# luci2_device.net
KiCad netlist of a schematic drawn in EAGLE
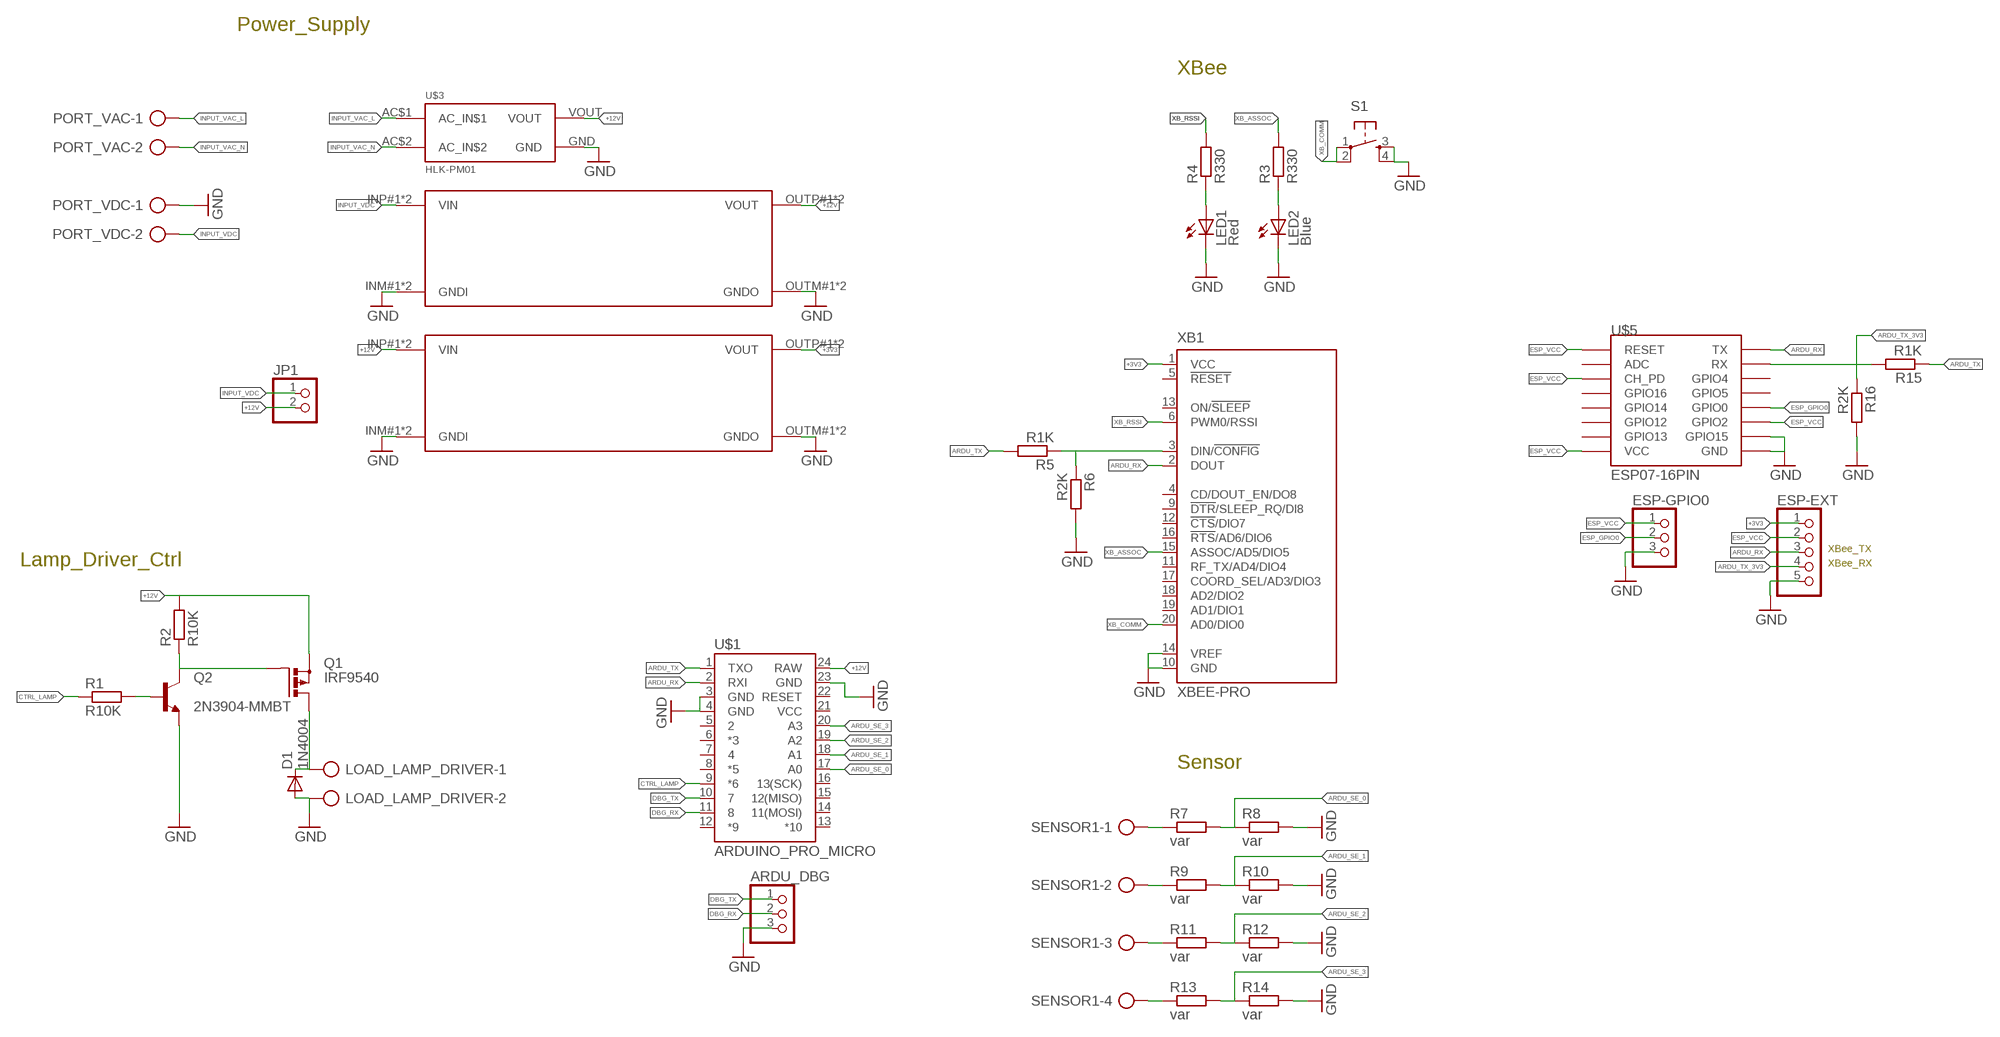
[diagram p0: schematic, sheet 1]

(export (version "E")
  (design (tool "Eeschema 10.0.6"))
  (components
    (comp (ref "ARDU_DBG")
      (value "HEADER-1X3ROUND")
      (footprint "eagle-import:1X03_ROUND")
      (libsource (lib "eagle-import") (part "HEADER-1X3ROUND"))
    )
    (comp (ref "D1")
      (value "1N4004")
      (footprint "eagle-import:DO41-10")
      (libsource (lib "eagle-import") (part "1N4004"))
    )
    (comp (ref "ESP-EXT")
      (value "HEADER-1X5ROUND")
      (footprint "eagle-import:1X05_ROUND")
      (libsource (lib "eagle-import") (part "HEADER-1X5ROUND"))
    )
    (comp (ref "ESP-GPIO0")
      (value "HEADER-1X3ROUND")
      (footprint "eagle-import:1X03_ROUND")
      (libsource (lib "eagle-import") (part "HEADER-1X3ROUND"))
    )
    (comp (ref "JP1")
      (value "HEADER-1X2ROUND")
      (footprint "eagle-import:1X02_ROUND")
      (libsource (lib "eagle-import") (part "HEADER-1X2ROUND"))
    )
    (comp (ref "LED1")
      (value "Red")
      (footprint "eagle-import:CHIPLED_0805")
      (libsource (lib "eagle-import") (part "LEDCHIPLED_0805"))
    )
    (comp (ref "LED2")
      (value "Blue")
      (footprint "eagle-import:CHIPLED_0805")
      (libsource (lib "eagle-import") (part "LEDCHIPLED_0805"))
    )
    (comp (ref "LOAD_LAMP_DRIVER")
      (value "AK300/2")
      (footprint "eagle-import:AK300_2")
      (libsource (lib "eagle-import") (part "AK300/2"))
    )
    (comp (ref "PORT_VAC")
      (value "AK300/2")
      (footprint "eagle-import:AK300_2")
      (libsource (lib "eagle-import") (part "AK300/2"))
    )
    (comp (ref "PORT_VDC")
      (value "AK300/2")
      (footprint "eagle-import:AK300_2")
      (libsource (lib "eagle-import") (part "AK300/2"))
    )
    (comp (ref "Q1")
      (value "IRF9540")
      (footprint "eagle-import:TO220BV")
      (libsource (lib "eagle-import") (part "PMOSFET_PTO220BV"))
    )
    (comp (ref "Q2")
      (value "2N3904-MMBT")
      (footprint "eagle-import:SOT23")
      (libsource (lib "eagle-import") (part "2N3904-MMBT"))
    )
    (comp (ref "R1")
      (value "R10K")
      (footprint "eagle-import:M0805")
      (libsource (lib "eagle-import") (part "R-EU_M0805"))
    )
    (comp (ref "R2")
      (value "R10K")
      (footprint "eagle-import:M0805")
      (libsource (lib "eagle-import") (part "R-EU_M0805"))
    )
    (comp (ref "R3")
      (value "R330")
      (footprint "eagle-import:M0805")
      (libsource (lib "eagle-import") (part "R-EU_M0805"))
    )
    (comp (ref "R4")
      (value "R330")
      (footprint "eagle-import:M0805")
      (libsource (lib "eagle-import") (part "R-EU_M0805"))
    )
    (comp (ref "R5")
      (value "R1K")
      (footprint "eagle-import:M0805")
      (libsource (lib "eagle-import") (part "R-EU_M0805"))
    )
    (comp (ref "R6")
      (value "R2K")
      (footprint "eagle-import:M0805")
      (libsource (lib "eagle-import") (part "R-EU_M0805"))
    )
    (comp (ref "R7")
      (value "var")
      (footprint "eagle-import:M0805")
      (libsource (lib "eagle-import") (part "R-EU_M0805"))
    )
    (comp (ref "R8")
      (value "var")
      (footprint "eagle-import:M0805")
      (libsource (lib "eagle-import") (part "R-EU_M0805"))
    )
    (comp (ref "R9")
      (value "var")
      (footprint "eagle-import:M0805")
      (libsource (lib "eagle-import") (part "R-EU_M0805"))
    )
    (comp (ref "R10")
      (value "var")
      (footprint "eagle-import:M0805")
      (libsource (lib "eagle-import") (part "R-EU_M0805"))
    )
    (comp (ref "R11")
      (value "var")
      (footprint "eagle-import:M0805")
      (libsource (lib "eagle-import") (part "R-EU_M0805"))
    )
    (comp (ref "R12")
      (value "var")
      (footprint "eagle-import:M0805")
      (libsource (lib "eagle-import") (part "R-EU_M0805"))
    )
    (comp (ref "R13")
      (value "var")
      (footprint "eagle-import:M0805")
      (libsource (lib "eagle-import") (part "R-EU_M0805"))
    )
    (comp (ref "R14")
      (value "var")
      (footprint "eagle-import:M0805")
      (libsource (lib "eagle-import") (part "R-EU_M0805"))
    )
    (comp (ref "R15")
      (value "R1K")
      (footprint "eagle-import:M0805")
      (libsource (lib "eagle-import") (part "R-EU_M0805"))
    )
    (comp (ref "R16")
      (value "R2K")
      (footprint "eagle-import:M0805")
      (libsource (lib "eagle-import") (part "R-EU_M0805"))
    )
    (comp (ref "S1")
      (value "TAC_SWITCHPTH")
      (footprint "eagle-import:TACTILE-PTH")
      (libsource (lib "eagle-import") (part "TAC_SWITCHPTH"))
    )
    (comp (ref "SENSOR1")
      (value "AK300/4")
      (footprint "eagle-import:AK300_4")
      (libsource (lib "eagle-import") (part "AK300/4"))
    )
    (comp (ref "U$1")
      (value "ARDUINO_PRO_MICRO")
      (footprint "eagle-import:ARDUINO_PRO_MICRO")
      (libsource (lib "eagle-import") (part "ARDUINO_PRO_MICRO"))
    )
    (comp (ref "U$2")
      (value "DCDCMODULE_SMALL")
      (footprint "eagle-import:DCDCMODULE-SMALL")
      (libsource (lib "eagle-import") (part "DCDCMODULE_SMALL"))
    )
    (comp (ref "U$3")
      (value "HLK-PM01")
      (footprint "eagle-import:HLK-PM01")
      (libsource (lib "eagle-import") (part "HLK-PM01"))
    )
    (comp (ref "U$4")
      (value "DCDCMODULE_SMALL")
      (footprint "eagle-import:DCDCMODULE-SMALL")
      (libsource (lib "eagle-import") (part "DCDCMODULE_SMALL"))
    )
    (comp (ref "U$5")
      (value "ESP07-16PIN")
      (footprint "eagle-import:ESP07-16PIN")
      (libsource (lib "eagle-import") (part "ESP07-16PIN"))
    )
    (comp (ref "XB1")
      (value "XBEE-PRO")
      (footprint "eagle-import:XBEE-PRO")
      (libsource (lib "eagle-import") (part "XBEE-PRO"))
    )
  )
  (nets
    (net (code "1") (name "+3V3") (class "Default")
      (node (ref "ESP-EXT") (pin "1") (pinfunction "1_1") (pintype "passive"))
      (node (ref "U$2") (pin "OUTP#1") (pinfunction "VOUT_OUTP#1") (pintype "bidirectional"))
      (node (ref "U$2") (pin "OUTP#2") (pinfunction "VOUT_OUTP#2") (pintype "bidirectional"))
      (node (ref "XB1") (pin "1") (pinfunction "VCC_1") (pintype "power_in"))
    )
    (net (code "2") (name "+12V") (class "Default")
      (node (ref "JP1") (pin "2") (pinfunction "2_2") (pintype "passive"))
      (node (ref "Q1") (pin "S") (pinfunction "S_S") (pintype "passive"))
      (node (ref "R2") (pin "2") (pinfunction "2_2") (pintype "passive"))
      (node (ref "U$1") (pin "24") (pinfunction "RAW_24") (pintype "bidirectional"))
      (node (ref "U$2") (pin "INP#1") (pinfunction "VIN_INP#1") (pintype "bidirectional"))
      (node (ref "U$2") (pin "INP#2") (pinfunction "VIN_INP#2") (pintype "bidirectional"))
      (node (ref "U$3") (pin "VOUT") (pinfunction "VOUT_VOUT") (pintype "bidirectional"))
      (node (ref "U$4") (pin "OUTP#1") (pinfunction "VOUT_OUTP#1") (pintype "bidirectional"))
      (node (ref "U$4") (pin "OUTP#2") (pinfunction "VOUT_OUTP#2") (pintype "bidirectional"))
    )
    (net (code "3") (name "ARDU_RX") (class "Default")
      (node (ref "ESP-EXT") (pin "3") (pinfunction "3_3") (pintype "passive"))
      (node (ref "U$1") (pin "2") (pinfunction "RXI_2") (pintype "bidirectional"))
      (node (ref "U$5") (pin "TX") (pinfunction "TX_TX") (pintype "bidirectional"))
      (node (ref "XB1") (pin "2") (pinfunction "DOUT_2") (pintype "output"))
    )
    (net (code "4") (name "ARDU_SE_0") (class "Default")
      (node (ref "R7") (pin "2") (pinfunction "2_2") (pintype "passive"))
      (node (ref "R8") (pin "1") (pinfunction "1_1") (pintype "passive"))
      (node (ref "U$1") (pin "17") (pinfunction "A0_17") (pintype "bidirectional"))
    )
    (net (code "5") (name "ARDU_SE_1") (class "Default")
      (node (ref "R10") (pin "1") (pinfunction "1_1") (pintype "passive"))
      (node (ref "R9") (pin "2") (pinfunction "2_2") (pintype "passive"))
      (node (ref "U$1") (pin "18") (pinfunction "A1_18") (pintype "bidirectional"))
    )
    (net (code "6") (name "ARDU_SE_2") (class "Default")
      (node (ref "R11") (pin "2") (pinfunction "2_2") (pintype "passive"))
      (node (ref "R12") (pin "1") (pinfunction "1_1") (pintype "passive"))
      (node (ref "U$1") (pin "19") (pinfunction "A2_19") (pintype "bidirectional"))
    )
    (net (code "7") (name "ARDU_SE_3") (class "Default")
      (node (ref "R13") (pin "2") (pinfunction "2_2") (pintype "passive"))
      (node (ref "R14") (pin "1") (pinfunction "1_1") (pintype "passive"))
      (node (ref "U$1") (pin "20") (pinfunction "A3_20") (pintype "bidirectional"))
    )
    (net (code "8") (name "ARDU_TX") (class "Default")
      (node (ref "R15") (pin "1") (pinfunction "1_1") (pintype "passive"))
      (node (ref "R5") (pin "2") (pinfunction "2_2") (pintype "passive"))
      (node (ref "U$1") (pin "1") (pinfunction "TXO_1") (pintype "bidirectional"))
    )
    (net (code "9") (name "ARDU_TX_3V3") (class "Default")
      (node (ref "ESP-EXT") (pin "4") (pinfunction "4_4") (pintype "passive"))
      (node (ref "R15") (pin "2") (pinfunction "2_2") (pintype "passive"))
      (node (ref "R16") (pin "1") (pinfunction "1_1") (pintype "passive"))
      (node (ref "U$5") (pin "RX") (pinfunction "RX_RX") (pintype "bidirectional"))
    )
    (net (code "10") (name "CTRL_LAMP") (class "Default")
      (node (ref "R1") (pin "1") (pinfunction "1_1") (pintype "passive"))
      (node (ref "U$1") (pin "9") (pinfunction "*6_9") (pintype "bidirectional"))
    )
    (net (code "11") (name "DBG_RX") (class "Default")
      (node (ref "ARDU_DBG") (pin "2") (pinfunction "2_2") (pintype "passive"))
      (node (ref "U$1") (pin "11") (pinfunction "8_11") (pintype "bidirectional"))
    )
    (net (code "12") (name "DBG_TX") (class "Default")
      (node (ref "ARDU_DBG") (pin "1") (pinfunction "1_1") (pintype "passive"))
      (node (ref "U$1") (pin "10") (pinfunction "7_10") (pintype "bidirectional"))
    )
    (net (code "13") (name "ESP_GPIO0") (class "Default")
      (node (ref "ESP-GPIO0") (pin "2") (pinfunction "2_2") (pintype "passive"))
      (node (ref "U$5") (pin "GPIO0") (pinfunction "GPIO0_GPIO0") (pintype "bidirectional"))
    )
    (net (code "14") (name "ESP_VCC") (class "Default")
      (node (ref "ESP-EXT") (pin "2") (pinfunction "2_2") (pintype "passive"))
      (node (ref "ESP-GPIO0") (pin "1") (pinfunction "1_1") (pintype "passive"))
      (node (ref "U$5") (pin "CH_PD") (pinfunction "CH_PD_CH_PD") (pintype "bidirectional"))
      (node (ref "U$5") (pin "GPIO2") (pinfunction "GPIO2_GPIO2") (pintype "bidirectional"))
      (node (ref "U$5") (pin "REST") (pinfunction "RESET_REST") (pintype "bidirectional"))
      (node (ref "U$5") (pin "VCC") (pinfunction "VCC_VCC") (pintype "bidirectional"))
    )
    (net (code "15") (name "GND") (class "Default")
      (node (ref "ARDU_DBG") (pin "3") (pinfunction "3_3") (pintype "passive"))
      (node (ref "D1") (pin "A") (pinfunction "A_A") (pintype "passive"))
      (node (ref "ESP-EXT") (pin "5") (pinfunction "5_5") (pintype "passive"))
      (node (ref "ESP-GPIO0") (pin "3") (pinfunction "3_3") (pintype "passive"))
      (node (ref "LED1") (pin "C") (pinfunction "C_C") (pintype "passive"))
      (node (ref "LED2") (pin "C") (pinfunction "C_C") (pintype "passive"))
      (node (ref "LOAD_LAMP_DRIVER") (pin "2") (pinfunction "KL_2") (pintype "passive"))
      (node (ref "PORT_VDC") (pin "1") (pinfunction "KL_1") (pintype "passive"))
      (node (ref "Q2") (pin "2") (pinfunction "E_2") (pintype "passive"))
      (node (ref "R10") (pin "2") (pinfunction "2_2") (pintype "passive"))
      (node (ref "R12") (pin "2") (pinfunction "2_2") (pintype "passive"))
      (node (ref "R14") (pin "2") (pinfunction "2_2") (pintype "passive"))
      (node (ref "R16") (pin "2") (pinfunction "2_2") (pintype "passive"))
      (node (ref "R6") (pin "2") (pinfunction "2_2") (pintype "passive"))
      (node (ref "R8") (pin "2") (pinfunction "2_2") (pintype "passive"))
      (node (ref "S1") (pin "3") (pinfunction "3_3") (pintype "passive"))
      (node (ref "S1") (pin "4") (pinfunction "4_4") (pintype "passive"))
      (node (ref "U$1") (pin "23") (pinfunction "GND_23") (pintype "bidirectional"))
      (node (ref "U$1") (pin "3") (pinfunction "GND_3") (pintype "bidirectional"))
      (node (ref "U$1") (pin "4") (pinfunction "GND_4") (pintype "bidirectional"))
      (node (ref "U$2") (pin "INM#1") (pinfunction "GNDI_INM#1") (pintype "bidirectional"))
      (node (ref "U$2") (pin "INM#2") (pinfunction "GNDI_INM#2") (pintype "bidirectional"))
      (node (ref "U$2") (pin "OUTM#1") (pinfunction "GNDO_OUTM#1") (pintype "bidirectional"))
      (node (ref "U$2") (pin "OUTM#2") (pinfunction "GNDO_OUTM#2") (pintype "bidirectional"))
      (node (ref "U$3") (pin "GND") (pinfunction "GND_GND") (pintype "bidirectional"))
      (node (ref "U$4") (pin "INM#1") (pinfunction "GNDI_INM#1") (pintype "bidirectional"))
      (node (ref "U$4") (pin "INM#2") (pinfunction "GNDI_INM#2") (pintype "bidirectional"))
      (node (ref "U$4") (pin "OUTM#1") (pinfunction "GNDO_OUTM#1") (pintype "bidirectional"))
      (node (ref "U$4") (pin "OUTM#2") (pinfunction "GNDO_OUTM#2") (pintype "bidirectional"))
      (node (ref "U$5") (pin "GND") (pinfunction "GND_GND") (pintype "bidirectional"))
      (node (ref "U$5") (pin "GPIO15") (pinfunction "GPIO15_GPIO15") (pintype "bidirectional"))
      (node (ref "XB1") (pin "10") (pinfunction "GND_10") (pintype "power_in"))
      (node (ref "XB1") (pin "14") (pinfunction "VREF_14") (pintype "input"))
    )
    (net (code "16") (name "INPUT_VAC_L") (class "Default")
      (node (ref "PORT_VAC") (pin "1") (pinfunction "KL_1") (pintype "passive"))
      (node (ref "U$3") (pin "AC$1") (pinfunction "AC_IN$1_AC$1") (pintype "bidirectional"))
    )
    (net (code "17") (name "INPUT_VAC_N") (class "Default")
      (node (ref "PORT_VAC") (pin "2") (pinfunction "KL_2") (pintype "passive"))
      (node (ref "U$3") (pin "AC$2") (pinfunction "AC_IN$2_AC$2") (pintype "bidirectional"))
    )
    (net (code "18") (name "INPUT_VDC") (class "Default")
      (node (ref "JP1") (pin "1") (pinfunction "1_1") (pintype "passive"))
      (node (ref "PORT_VDC") (pin "2") (pinfunction "KL_2") (pintype "passive"))
      (node (ref "U$4") (pin "INP#1") (pinfunction "VIN_INP#1") (pintype "bidirectional"))
      (node (ref "U$4") (pin "INP#2") (pinfunction "VIN_INP#2") (pintype "bidirectional"))
    )
    (net (code "19") (name "Net-(LED1-PadA)") (class "Default")
      (node (ref "LED1") (pin "A") (pinfunction "A_A") (pintype "passive"))
      (node (ref "R4") (pin "1") (pinfunction "1_1") (pintype "passive"))
    )
    (net (code "20") (name "Net-(LED2-PadA)") (class "Default")
      (node (ref "LED2") (pin "A") (pinfunction "A_A") (pintype "passive"))
      (node (ref "R3") (pin "1") (pinfunction "1_1") (pintype "passive"))
    )
    (net (code "21") (name "Net-(LOAD_LAMP_DRIVERA-KL)") (class "Default")
      (node (ref "D1") (pin "C") (pinfunction "C_C") (pintype "passive"))
      (node (ref "LOAD_LAMP_DRIVER") (pin "1") (pinfunction "KL_1") (pintype "passive"))
      (node (ref "Q1") (pin "D") (pinfunction "D_D") (pintype "passive"))
    )
    (net (code "22") (name "Net-(Q2-B)") (class "Default")
      (node (ref "Q2") (pin "1") (pinfunction "B_1") (pintype "passive"))
      (node (ref "R1") (pin "2") (pinfunction "2_2") (pintype "passive"))
    )
    (net (code "23") (name "Net-(Q2-C)") (class "Default")
      (node (ref "Q1") (pin "G") (pinfunction "G_G") (pintype "passive"))
      (node (ref "Q2") (pin "3") (pinfunction "C_3") (pintype "passive"))
      (node (ref "R2") (pin "1") (pinfunction "1_1") (pintype "passive"))
    )
    (net (code "24") (name "Net-(SENSOR1A-KL)") (class "Default")
      (node (ref "R7") (pin "1") (pinfunction "1_1") (pintype "passive"))
      (node (ref "SENSOR1") (pin "1") (pinfunction "KL_1") (pintype "passive"))
    )
    (net (code "25") (name "Net-(SENSOR1B-KL)") (class "Default")
      (node (ref "R9") (pin "1") (pinfunction "1_1") (pintype "passive"))
      (node (ref "SENSOR1") (pin "2") (pinfunction "KL_2") (pintype "passive"))
    )
    (net (code "26") (name "Net-(SENSOR1C-KL)") (class "Default")
      (node (ref "R11") (pin "1") (pinfunction "1_1") (pintype "passive"))
      (node (ref "SENSOR1") (pin "3") (pinfunction "KL_3") (pintype "passive"))
    )
    (net (code "27") (name "Net-(SENSOR1D-KL)") (class "Default")
      (node (ref "R13") (pin "1") (pinfunction "1_1") (pintype "passive"))
      (node (ref "SENSOR1") (pin "4") (pinfunction "KL_4") (pintype "passive"))
    )
    (net (code "28") (name "Net-(XB1-DIN{slash}~{CONFIG})") (class "Default")
      (node (ref "R5") (pin "1") (pinfunction "1_1") (pintype "passive"))
      (node (ref "R6") (pin "1") (pinfunction "1_1") (pintype "passive"))
      (node (ref "XB1") (pin "3") (pinfunction "DIN/~{CONFIG}_3") (pintype "input"))
    )
    (net (code "29") (name "XB_ASSOC") (class "Default")
      (node (ref "R3") (pin "2") (pinfunction "2_2") (pintype "passive"))
      (node (ref "XB1") (pin "15") (pinfunction "ASSOC/AD5/DIO5_15") (pintype "bidirectional"))
    )
    (net (code "30") (name "XB_COMM") (class "Default")
      (node (ref "S1") (pin "1") (pinfunction "1_1") (pintype "passive"))
      (node (ref "S1") (pin "2") (pinfunction "2_2") (pintype "passive"))
      (node (ref "XB1") (pin "20") (pinfunction "AD0/DIO0_20") (pintype "bidirectional"))
    )
    (net (code "31") (name "XB_RSSI") (class "Default")
      (node (ref "R4") (pin "2") (pinfunction "2_2") (pintype "passive"))
      (node (ref "XB1") (pin "6") (pinfunction "PWM0/RSSI_6") (pintype "output"))
    )
    (net (code "32") (name "unconnected-(U$1-*3-Pad6)") (class "Default")
      (node (ref "U$1") (pin "6") (pinfunction "*3_6") (pintype "bidirectional"))
    )
    (net (code "33") (name "unconnected-(U$1-*5-Pad8)") (class "Default")
      (node (ref "U$1") (pin "8") (pinfunction "*5_8") (pintype "bidirectional"))
    )
    (net (code "34") (name "unconnected-(U$1-*9-Pad12)") (class "Default")
      (node (ref "U$1") (pin "12") (pinfunction "*9_12") (pintype "bidirectional"))
    )
    (net (code "35") (name "unconnected-(U$1-*10-Pad13)") (class "Default")
      (node (ref "U$1") (pin "13") (pinfunction "*10_13") (pintype "bidirectional"))
    )
    (net (code "36") (name "unconnected-(U$1-2-Pad5)") (class "Default")
      (node (ref "U$1") (pin "5") (pinfunction "2_5") (pintype "bidirectional"))
    )
    (net (code "37") (name "unconnected-(U$1-4-Pad7)") (class "Default")
      (node (ref "U$1") (pin "7") (pinfunction "4_7") (pintype "bidirectional"))
    )
    (net (code "38") (name "unconnected-(U$1-11(MOSI)-Pad14)") (class "Default")
      (node (ref "U$1") (pin "14") (pinfunction "11(MOSI)_14") (pintype "bidirectional"))
    )
    (net (code "39") (name "unconnected-(U$1-12(MISO)-Pad15)") (class "Default")
      (node (ref "U$1") (pin "15") (pinfunction "12(MISO)_15") (pintype "bidirectional"))
    )
    (net (code "40") (name "unconnected-(U$1-13(SCK)-Pad16)") (class "Default")
      (node (ref "U$1") (pin "16") (pinfunction "13(SCK)_16") (pintype "bidirectional"))
    )
    (net (code "41") (name "unconnected-(U$1-RESET-Pad22)") (class "Default")
      (node (ref "U$1") (pin "22") (pinfunction "RESET_22") (pintype "bidirectional"))
    )
    (net (code "42") (name "unconnected-(U$1-VCC-Pad21)") (class "Default")
      (node (ref "U$1") (pin "21") (pinfunction "VCC_21") (pintype "bidirectional"))
    )
    (net (code "43") (name "unconnected-(U$5-PadADC)") (class "Default")
      (node (ref "U$5") (pin "ADC") (pinfunction "ADC_ADC") (pintype "bidirectional"))
    )
    (net (code "44") (name "unconnected-(U$5-PadGPIO4)") (class "Default")
      (node (ref "U$5") (pin "GPIO4") (pinfunction "GPIO4_GPIO4") (pintype "bidirectional"))
    )
    (net (code "45") (name "unconnected-(U$5-PadGPIO5)") (class "Default")
      (node (ref "U$5") (pin "GPIO5") (pinfunction "GPIO5_GPIO5") (pintype "bidirectional"))
    )
    (net (code "46") (name "unconnected-(U$5-PadGPIO12)") (class "Default")
      (node (ref "U$5") (pin "GPIO12") (pinfunction "GPIO12_GPIO12") (pintype "bidirectional"))
    )
    (net (code "47") (name "unconnected-(U$5-PadGPIO13)") (class "Default")
      (node (ref "U$5") (pin "GPIO13") (pinfunction "GPIO13_GPIO13") (pintype "bidirectional"))
    )
    (net (code "48") (name "unconnected-(U$5-PadGPIO14)") (class "Default")
      (node (ref "U$5") (pin "GPIO14") (pinfunction "GPIO14_GPIO14") (pintype "bidirectional"))
    )
    (net (code "49") (name "unconnected-(U$5-PadGPIO16)") (class "Default")
      (node (ref "U$5") (pin "GPIO16") (pinfunction "GPIO16_GPIO16") (pintype "bidirectional"))
    )
    (net (code "50") (name "unconnected-(XB1-AD1{slash}DIO1-Pad19)") (class "Default")
      (node (ref "XB1") (pin "19") (pinfunction "AD1/DIO1_19") (pintype "bidirectional"))
    )
    (net (code "51") (name "unconnected-(XB1-AD2{slash}DIO2-Pad18)") (class "Default")
      (node (ref "XB1") (pin "18") (pinfunction "AD2/DIO2_18") (pintype "bidirectional"))
    )
    (net (code "52") (name "unconnected-(XB1-CD{slash}DOUT_EN{slash}DO8-Pad4)") (class "Default")
      (node (ref "XB1") (pin "4") (pinfunction "CD/DOUT_EN/DO8_4") (pintype "output"))
    )
    (net (code "53") (name "unconnected-(XB1-COORD_SEL{slash}AD3{slash}DIO3-Pad17)") (class "Default")
      (node (ref "XB1") (pin "17") (pinfunction "COORD_SEL/AD3/DIO3_17") (pintype "bidirectional"))
    )
    (net (code "54") (name "unconnected-(XB1-ON{slash}~{SLEEP}-Pad13)") (class "Default")
      (node (ref "XB1") (pin "13") (pinfunction "ON/~{SLEEP}_13") (pintype "output"))
    )
    (net (code "55") (name "unconnected-(XB1-RF_TX{slash}AD4{slash}DIO4-Pad11)") (class "Default")
      (node (ref "XB1") (pin "11") (pinfunction "RF_TX/AD4/DIO4_11") (pintype "bidirectional"))
    )
    (net (code "56") (name "unconnected-(XB1-~{CTS}{slash}DIO7-Pad12)") (class "Default")
      (node (ref "XB1") (pin "12") (pinfunction "~{CTS}/DIO7_12") (pintype "bidirectional"))
    )
    (net (code "57") (name "unconnected-(XB1-~{DTR}{slash}SLEEP_RQ{slash}DI8-Pad9)") (class "Default")
      (node (ref "XB1") (pin "9") (pinfunction "~{DTR}/SLEEP_RQ/DI8_9") (pintype "bidirectional"))
    )
    (net (code "58") (name "unconnected-(XB1-~{RESET}-Pad5)") (class "Default")
      (node (ref "XB1") (pin "5") (pinfunction "~{RESET}_5") (pintype "input"))
    )
    (net (code "59") (name "unconnected-(XB1-~{RTS}{slash}AD6{slash}DIO6-Pad16)") (class "Default")
      (node (ref "XB1") (pin "16") (pinfunction "~{RTS}/AD6/DIO6_16") (pintype "bidirectional"))
    )
  )
)
